# ds32djg.net
KiCad netlist of a schematic drawn in EAGLE
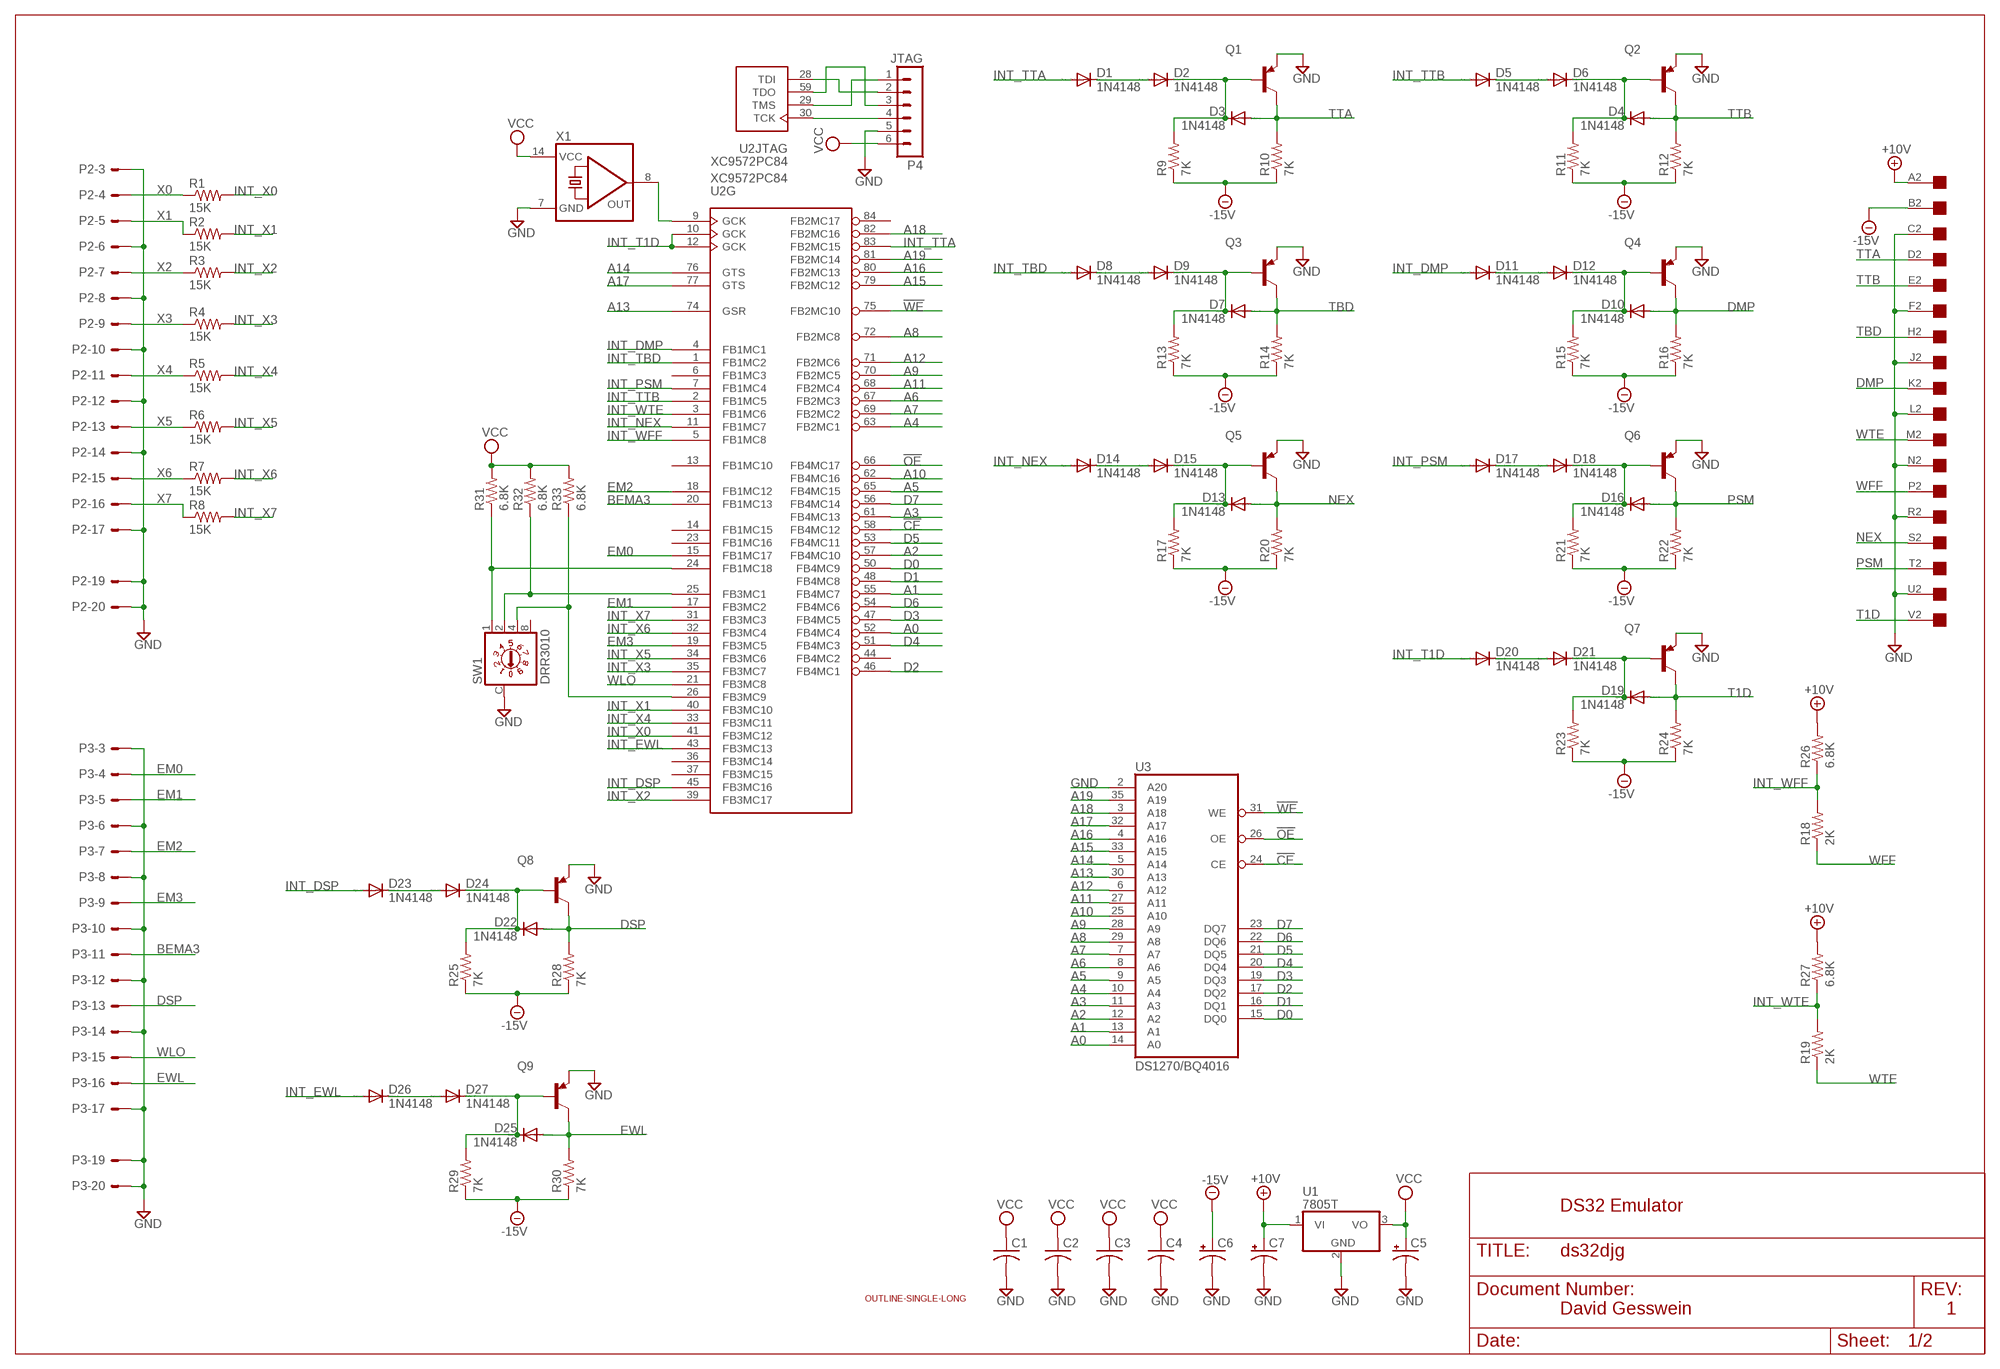
[diagram p0: schematic, sheet 1]
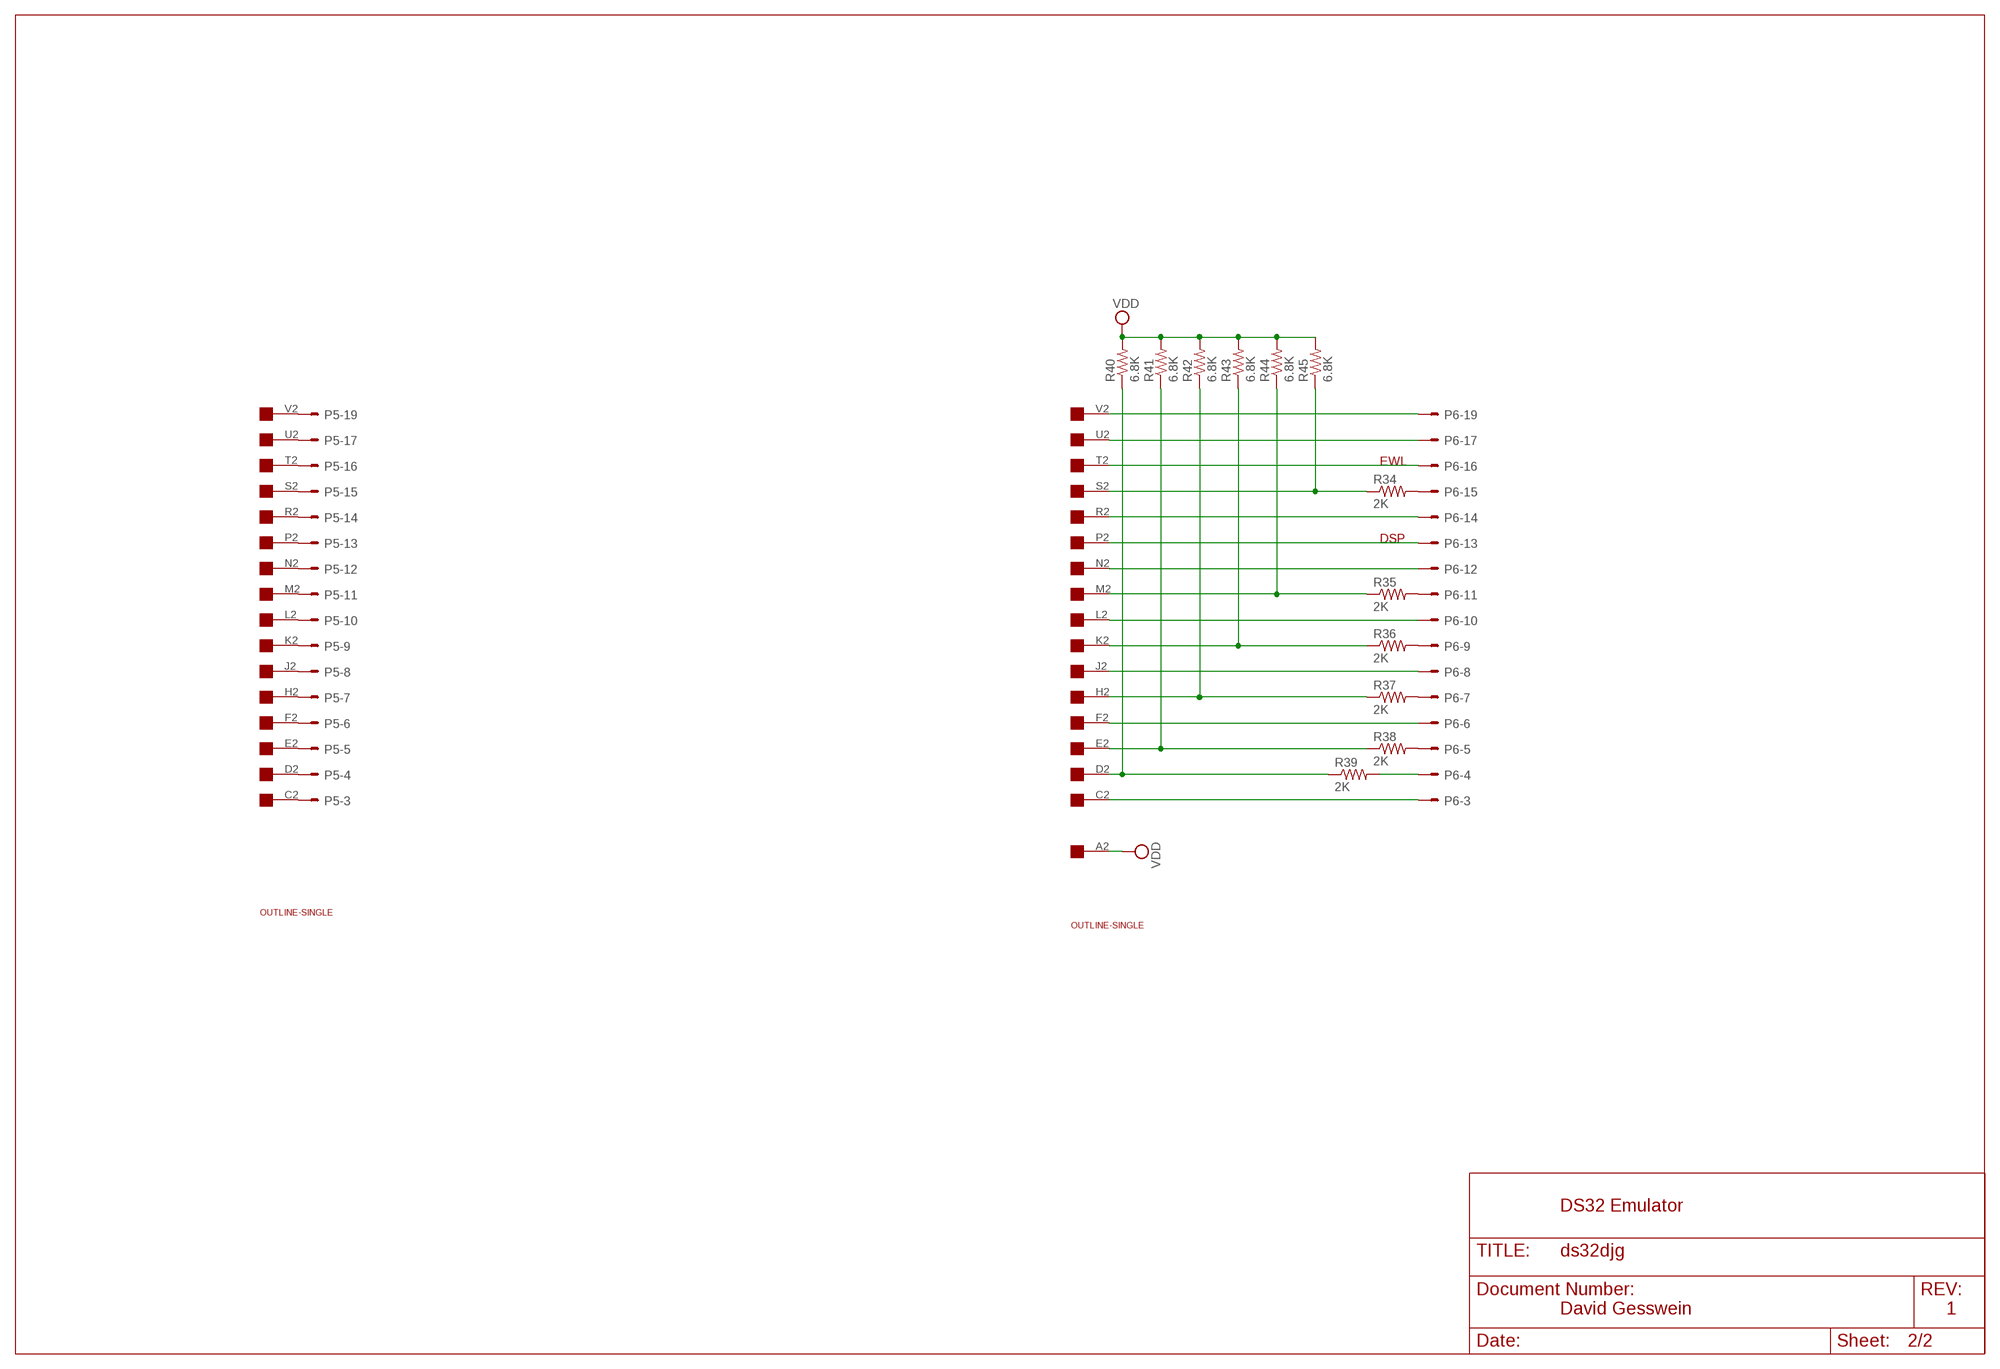
[diagram p1: schematic, sheet 2]

(export (version "E")
  (design (tool "Eeschema 10.0.6"))
  (components
    (comp (ref "P5")
      (value "ML20E")
      (footprint "eagle-import:ML20")
      (libsource (lib "eagle-import") (part "ML20?E"))
    )
    (comp (ref "P6")
      (value "ML20E")
      (footprint "eagle-import:ML20")
      (libsource (lib "eagle-import") (part "ML20?E"))
    )
    (comp (ref "R34")
      (value "2K")
      (footprint "eagle-import:0207_10")
      (libsource (lib "eagle-import") (part "R-US_0207/10"))
    )
    (comp (ref "R35")
      (value "2K")
      (footprint "eagle-import:0207_10")
      (libsource (lib "eagle-import") (part "R-US_0207/10"))
    )
    (comp (ref "R36")
      (value "2K")
      (footprint "eagle-import:0207_10")
      (libsource (lib "eagle-import") (part "R-US_0207/10"))
    )
    (comp (ref "R37")
      (value "2K")
      (footprint "eagle-import:0207_10")
      (libsource (lib "eagle-import") (part "R-US_0207/10"))
    )
    (comp (ref "R38")
      (value "2K")
      (footprint "eagle-import:0207_10")
      (libsource (lib "eagle-import") (part "R-US_0207/10"))
    )
    (comp (ref "R39")
      (value "2K")
      (footprint "eagle-import:0207_10")
      (libsource (lib "eagle-import") (part "R-US_0207/10"))
    )
    (comp (ref "R40")
      (value "6.8K")
      (footprint "eagle-import:0207_10")
      (libsource (lib "eagle-import") (part "R-US_0207/10"))
    )
    (comp (ref "R41")
      (value "6.8K")
      (footprint "eagle-import:0207_10")
      (libsource (lib "eagle-import") (part "R-US_0207/10"))
    )
    (comp (ref "R42")
      (value "6.8K")
      (footprint "eagle-import:0207_10")
      (libsource (lib "eagle-import") (part "R-US_0207/10"))
    )
    (comp (ref "R43")
      (value "6.8K")
      (footprint "eagle-import:0207_10")
      (libsource (lib "eagle-import") (part "R-US_0207/10"))
    )
    (comp (ref "R44")
      (value "6.8K")
      (footprint "eagle-import:0207_10")
      (libsource (lib "eagle-import") (part "R-US_0207/10"))
    )
    (comp (ref "R45")
      (value "6.8K")
      (footprint "eagle-import:0207_10")
      (libsource (lib "eagle-import") (part "R-US_0207/10"))
    )
    (comp (ref "U$1")
      (value "EDGE-1")
      (footprint "eagle-import:EDGE-CON1")
      (libsource (lib "eagle-import") (part "EDGE-1"))
    )
    (comp (ref "U$2")
      (value "EDGE-1")
      (footprint "eagle-import:EDGE-CON1")
      (libsource (lib "eagle-import") (part "EDGE-1"))
    )
    (comp (ref "U$4")
      (value "OUTLINE-SINGLE")
      (footprint "eagle-import:SINGLE")
      (libsource (lib "eagle-import") (part "OUTLINE-SINGLE"))
    )
    (comp (ref "U$5")
      (value "OUTLINE-SINGLE")
      (footprint "eagle-import:SINGLE")
      (libsource (lib "eagle-import") (part "OUTLINE-SINGLE"))
    )
    (comp (ref "C1")
      (value "C-US050-025X075")
      (footprint "eagle-import:C050-025X075")
      (libsource (lib "eagle-import") (part "C-US050-025X075"))
    )
    (comp (ref "C2")
      (value "C-US050-025X075")
      (footprint "eagle-import:C050-025X075")
      (libsource (lib "eagle-import") (part "C-US050-025X075"))
    )
    (comp (ref "C3")
      (value "C-US050-025X075")
      (footprint "eagle-import:C050-025X075")
      (libsource (lib "eagle-import") (part "C-US050-025X075"))
    )
    (comp (ref "C4")
      (value "C-US050-025X075")
      (footprint "eagle-import:C050-025X075")
      (libsource (lib "eagle-import") (part "C-US050-025X075"))
    )
    (comp (ref "C5")
      (value "CPOL-USE15-5AXIAL")
      (footprint "eagle-import:E15-5")
      (libsource (lib "eagle-import") (part "CPOL-USE15-5AXIAL"))
    )
    (comp (ref "C6")
      (value "CPOL-USE15-5AXIAL")
      (footprint "eagle-import:E15-5")
      (libsource (lib "eagle-import") (part "CPOL-USE15-5AXIAL"))
    )
    (comp (ref "C7")
      (value "CPOL-USE15-5AXIAL")
      (footprint "eagle-import:E15-5")
      (libsource (lib "eagle-import") (part "CPOL-USE15-5AXIAL"))
    )
    (comp (ref "D1")
      (value "1N4148")
      (footprint "eagle-import:DO35-10")
      (libsource (lib "eagle-import") (part "1N4148DO35-10"))
    )
    (comp (ref "D2")
      (value "1N4148")
      (footprint "eagle-import:DO35-10")
      (libsource (lib "eagle-import") (part "1N4148DO35-10"))
    )
    (comp (ref "D3")
      (value "1N4148")
      (footprint "eagle-import:DO35-10")
      (libsource (lib "eagle-import") (part "1N4148DO35-10"))
    )
    (comp (ref "D4")
      (value "1N4148")
      (footprint "eagle-import:DO35-10")
      (libsource (lib "eagle-import") (part "1N4148DO35-10"))
    )
    (comp (ref "D5")
      (value "1N4148")
      (footprint "eagle-import:DO35-10")
      (libsource (lib "eagle-import") (part "1N4148DO35-10"))
    )
    (comp (ref "D6")
      (value "1N4148")
      (footprint "eagle-import:DO35-10")
      (libsource (lib "eagle-import") (part "1N4148DO35-10"))
    )
    (comp (ref "D7")
      (value "1N4148")
      (footprint "eagle-import:DO35-10")
      (libsource (lib "eagle-import") (part "1N4148DO35-10"))
    )
    (comp (ref "D8")
      (value "1N4148")
      (footprint "eagle-import:DO35-10")
      (libsource (lib "eagle-import") (part "1N4148DO35-10"))
    )
    (comp (ref "D9")
      (value "1N4148")
      (footprint "eagle-import:DO35-10")
      (libsource (lib "eagle-import") (part "1N4148DO35-10"))
    )
    (comp (ref "D10")
      (value "1N4148")
      (footprint "eagle-import:DO35-10")
      (libsource (lib "eagle-import") (part "1N4148DO35-10"))
    )
    (comp (ref "D11")
      (value "1N4148")
      (footprint "eagle-import:DO35-10")
      (libsource (lib "eagle-import") (part "1N4148DO35-10"))
    )
    (comp (ref "D12")
      (value "1N4148")
      (footprint "eagle-import:DO35-10")
      (libsource (lib "eagle-import") (part "1N4148DO35-10"))
    )
    (comp (ref "D13")
      (value "1N4148")
      (footprint "eagle-import:DO35-10")
      (libsource (lib "eagle-import") (part "1N4148DO35-10"))
    )
    (comp (ref "D14")
      (value "1N4148")
      (footprint "eagle-import:DO35-10")
      (libsource (lib "eagle-import") (part "1N4148DO35-10"))
    )
    (comp (ref "D15")
      (value "1N4148")
      (footprint "eagle-import:DO35-10")
      (libsource (lib "eagle-import") (part "1N4148DO35-10"))
    )
    (comp (ref "D16")
      (value "1N4148")
      (footprint "eagle-import:DO35-10")
      (libsource (lib "eagle-import") (part "1N4148DO35-10"))
    )
    (comp (ref "D17")
      (value "1N4148")
      (footprint "eagle-import:DO35-10")
      (libsource (lib "eagle-import") (part "1N4148DO35-10"))
    )
    (comp (ref "D18")
      (value "1N4148")
      (footprint "eagle-import:DO35-10")
      (libsource (lib "eagle-import") (part "1N4148DO35-10"))
    )
    (comp (ref "D19")
      (value "1N4148")
      (footprint "eagle-import:DO35-10")
      (libsource (lib "eagle-import") (part "1N4148DO35-10"))
    )
    (comp (ref "D20")
      (value "1N4148")
      (footprint "eagle-import:DO35-10")
      (libsource (lib "eagle-import") (part "1N4148DO35-10"))
    )
    (comp (ref "D21")
      (value "1N4148")
      (footprint "eagle-import:DO35-10")
      (libsource (lib "eagle-import") (part "1N4148DO35-10"))
    )
    (comp (ref "D22")
      (value "1N4148")
      (footprint "eagle-import:DO35-10")
      (libsource (lib "eagle-import") (part "1N4148DO35-10"))
    )
    (comp (ref "D23")
      (value "1N4148")
      (footprint "eagle-import:DO35-10")
      (libsource (lib "eagle-import") (part "1N4148DO35-10"))
    )
    (comp (ref "D24")
      (value "1N4148")
      (footprint "eagle-import:DO35-10")
      (libsource (lib "eagle-import") (part "1N4148DO35-10"))
    )
    (comp (ref "D25")
      (value "1N4148")
      (footprint "eagle-import:DO35-10")
      (libsource (lib "eagle-import") (part "1N4148DO35-10"))
    )
    (comp (ref "D26")
      (value "1N4148")
      (footprint "eagle-import:DO35-10")
      (libsource (lib "eagle-import") (part "1N4148DO35-10"))
    )
    (comp (ref "D27")
      (value "1N4148")
      (footprint "eagle-import:DO35-10")
      (libsource (lib "eagle-import") (part "1N4148DO35-10"))
    )
    (comp (ref "P1")
      (value "EDGE-1")
      (footprint "eagle-import:EDGE-CON1")
      (libsource (lib "eagle-import") (part "EDGE-1"))
    )
    (comp (ref "P2")
      (value "ML20E")
      (footprint "eagle-import:ML20")
      (libsource (lib "eagle-import") (part "ML20?E"))
    )
    (comp (ref "P3")
      (value "ML20E")
      (footprint "eagle-import:ML20")
      (libsource (lib "eagle-import") (part "ML20?E"))
    )
    (comp (ref "P4")
      (value "JTAG")
      (footprint "eagle-import:MA06-1")
      (libsource (lib "eagle-import") (part "MA06-1"))
    )
    (comp (ref "Q1")
      (value "-PNP-TO92/")
      (footprint "eagle-import:TO92_")
      (libsource (lib "eagle-import") (part "-PNP-TO92/"))
    )
    (comp (ref "Q2")
      (value "-PNP-TO92/")
      (footprint "eagle-import:TO92_")
      (libsource (lib "eagle-import") (part "-PNP-TO92/"))
    )
    (comp (ref "Q3")
      (value "-PNP-TO92/")
      (footprint "eagle-import:TO92_")
      (libsource (lib "eagle-import") (part "-PNP-TO92/"))
    )
    (comp (ref "Q4")
      (value "-PNP-TO92/")
      (footprint "eagle-import:TO92_")
      (libsource (lib "eagle-import") (part "-PNP-TO92/"))
    )
    (comp (ref "Q5")
      (value "-PNP-TO92/")
      (footprint "eagle-import:TO92_")
      (libsource (lib "eagle-import") (part "-PNP-TO92/"))
    )
    (comp (ref "Q6")
      (value "-PNP-TO92/")
      (footprint "eagle-import:TO92_")
      (libsource (lib "eagle-import") (part "-PNP-TO92/"))
    )
    (comp (ref "Q7")
      (value "-PNP-TO92/")
      (footprint "eagle-import:TO92_")
      (libsource (lib "eagle-import") (part "-PNP-TO92/"))
    )
    (comp (ref "Q8")
      (value "-PNP-TO92/")
      (footprint "eagle-import:TO92_")
      (libsource (lib "eagle-import") (part "-PNP-TO92/"))
    )
    (comp (ref "Q9")
      (value "-PNP-TO92/")
      (footprint "eagle-import:TO92_")
      (libsource (lib "eagle-import") (part "-PNP-TO92/"))
    )
    (comp (ref "R1")
      (value "15K")
      (footprint "eagle-import:0207_10")
      (libsource (lib "eagle-import") (part "R-US_0207/10"))
    )
    (comp (ref "R2")
      (value "15K")
      (footprint "eagle-import:0207_10")
      (libsource (lib "eagle-import") (part "R-US_0207/10"))
    )
    (comp (ref "R3")
      (value "15K")
      (footprint "eagle-import:0207_10")
      (libsource (lib "eagle-import") (part "R-US_0207/10"))
    )
    (comp (ref "R4")
      (value "15K")
      (footprint "eagle-import:0207_10")
      (libsource (lib "eagle-import") (part "R-US_0207/10"))
    )
    (comp (ref "R5")
      (value "15K")
      (footprint "eagle-import:0207_10")
      (libsource (lib "eagle-import") (part "R-US_0207/10"))
    )
    (comp (ref "R6")
      (value "15K")
      (footprint "eagle-import:0207_10")
      (libsource (lib "eagle-import") (part "R-US_0207/10"))
    )
    (comp (ref "R7")
      (value "15K")
      (footprint "eagle-import:0207_10")
      (libsource (lib "eagle-import") (part "R-US_0207/10"))
    )
    (comp (ref "R8")
      (value "15K")
      (footprint "eagle-import:0207_10")
      (libsource (lib "eagle-import") (part "R-US_0207/10"))
    )
    (comp (ref "R9")
      (value "7K")
      (footprint "eagle-import:0207_10")
      (libsource (lib "eagle-import") (part "R-US_0207/10"))
    )
    (comp (ref "R10")
      (value "7K")
      (footprint "eagle-import:0207_10")
      (libsource (lib "eagle-import") (part "R-US_0207/10"))
    )
    (comp (ref "R11")
      (value "7K")
      (footprint "eagle-import:0207_10")
      (libsource (lib "eagle-import") (part "R-US_0207/10"))
    )
    (comp (ref "R12")
      (value "7K")
      (footprint "eagle-import:0207_10")
      (libsource (lib "eagle-import") (part "R-US_0207/10"))
    )
    (comp (ref "R13")
      (value "7K")
      (footprint "eagle-import:0207_10")
      (libsource (lib "eagle-import") (part "R-US_0207/10"))
    )
    (comp (ref "R14")
      (value "7K")
      (footprint "eagle-import:0207_10")
      (libsource (lib "eagle-import") (part "R-US_0207/10"))
    )
    (comp (ref "R15")
      (value "7K")
      (footprint "eagle-import:0207_10")
      (libsource (lib "eagle-import") (part "R-US_0207/10"))
    )
    (comp (ref "R16")
      (value "7K")
      (footprint "eagle-import:0207_10")
      (libsource (lib "eagle-import") (part "R-US_0207/10"))
    )
    (comp (ref "R17")
      (value "7K")
      (footprint "eagle-import:0207_10")
      (libsource (lib "eagle-import") (part "R-US_0207/10"))
    )
    (comp (ref "R18")
      (value "2K")
      (footprint "eagle-import:0207_10")
      (libsource (lib "eagle-import") (part "R-US_0207/10"))
    )
    (comp (ref "R19")
      (value "2K")
      (footprint "eagle-import:0207_10")
      (libsource (lib "eagle-import") (part "R-US_0207/10"))
    )
    (comp (ref "R20")
      (value "7K")
      (footprint "eagle-import:0207_10")
      (libsource (lib "eagle-import") (part "R-US_0207/10"))
    )
    (comp (ref "R21")
      (value "7K")
      (footprint "eagle-import:0207_10")
      (libsource (lib "eagle-import") (part "R-US_0207/10"))
    )
    (comp (ref "R22")
      (value "7K")
      (footprint "eagle-import:0207_10")
      (libsource (lib "eagle-import") (part "R-US_0207/10"))
    )
    (comp (ref "R23")
      (value "7K")
      (footprint "eagle-import:0207_10")
      (libsource (lib "eagle-import") (part "R-US_0207/10"))
    )
    (comp (ref "R24")
      (value "7K")
      (footprint "eagle-import:0207_10")
      (libsource (lib "eagle-import") (part "R-US_0207/10"))
    )
    (comp (ref "R25")
      (value "7K")
      (footprint "eagle-import:0207_10")
      (libsource (lib "eagle-import") (part "R-US_0207/10"))
    )
    (comp (ref "R26")
      (value "6.8K")
      (footprint "eagle-import:0207_10")
      (libsource (lib "eagle-import") (part "R-US_0207/10"))
    )
    (comp (ref "R27")
      (value "6.8K")
      (footprint "eagle-import:0207_10")
      (libsource (lib "eagle-import") (part "R-US_0207/10"))
    )
    (comp (ref "R28")
      (value "7K")
      (footprint "eagle-import:0207_10")
      (libsource (lib "eagle-import") (part "R-US_0207/10"))
    )
    (comp (ref "R29")
      (value "7K")
      (footprint "eagle-import:0207_10")
      (libsource (lib "eagle-import") (part "R-US_0207/10"))
    )
    (comp (ref "R30")
      (value "7K")
      (footprint "eagle-import:0207_10")
      (libsource (lib "eagle-import") (part "R-US_0207/10"))
    )
    (comp (ref "R31")
      (value "6.8K")
      (footprint "eagle-import:0207_10")
      (libsource (lib "eagle-import") (part "R-US_0207/10"))
    )
    (comp (ref "R32")
      (value "6.8K")
      (footprint "eagle-import:0207_10")
      (libsource (lib "eagle-import") (part "R-US_0207/10"))
    )
    (comp (ref "R33")
      (value "6.8K")
      (footprint "eagle-import:0207_10")
      (libsource (lib "eagle-import") (part "R-US_0207/10"))
    )
    (comp (ref "SW1")
      (value "DRR3010")
      (footprint "eagle-import:DRR3010")
      (libsource (lib "eagle-import") (part "DRR3010"))
    )
    (comp (ref "U$3")
      (value "OUTLINE-SINGLE-LONG")
      (footprint "eagle-import:SINGLE-LONG")
      (libsource (lib "eagle-import") (part "OUTLINE-SINGLE-LONG"))
    )
    (comp (ref "U1")
      (value "7805T")
      (footprint "eagle-import:TO220H")
      (libsource (lib "eagle-import") (part "78T05"))
    )
    (comp (ref "U2")
      (value "XC9572PC84")
      (footprint "eagle-import:PLCC-S84")
      (libsource (lib "eagle-import") (part "XC9572PC84"))
    )
    (comp (ref "U3")
      (value "DS1270/BQ4016")
      (footprint "eagle-import:MIL740EXT36")
      (libsource (lib "eagle-import") (part "DS1270"))
    )
    (comp (ref "X1")
      (value "QG5860")
      (footprint "eagle-import:DIL14S")
      (libsource (lib "eagle-import") (part "QG5860"))
    )
  )
  (nets
    (net (code "1") (name "+10V") (class "Default")
      (node (ref "C7") (pin "+") (pinfunction "+_+") (pintype "passive"))
      (node (ref "P1") (pin "A2") (pinfunction "1_A2") (pintype "bidirectional"))
      (node (ref "R26") (pin "2") (pinfunction "2_2") (pintype "passive"))
      (node (ref "R27") (pin "2") (pinfunction "2_2") (pintype "passive"))
      (node (ref "U1") (pin "1") (pinfunction "VI_1") (pintype "input"))
    )
    (net (code "2") (name "-15V") (class "Default")
      (node (ref "C6") (pin "+") (pinfunction "+_+") (pintype "passive"))
      (node (ref "P1") (pin "B2") (pinfunction "1_B2") (pintype "bidirectional"))
      (node (ref "R10") (pin "1") (pinfunction "1_1") (pintype "passive"))
      (node (ref "R11") (pin "1") (pinfunction "1_1") (pintype "passive"))
      (node (ref "R12") (pin "1") (pinfunction "1_1") (pintype "passive"))
      (node (ref "R13") (pin "1") (pinfunction "1_1") (pintype "passive"))
      (node (ref "R14") (pin "1") (pinfunction "1_1") (pintype "passive"))
      (node (ref "R15") (pin "1") (pinfunction "1_1") (pintype "passive"))
      (node (ref "R16") (pin "1") (pinfunction "1_1") (pintype "passive"))
      (node (ref "R17") (pin "1") (pinfunction "1_1") (pintype "passive"))
      (node (ref "R20") (pin "1") (pinfunction "1_1") (pintype "passive"))
      (node (ref "R21") (pin "1") (pinfunction "1_1") (pintype "passive"))
      (node (ref "R22") (pin "1") (pinfunction "1_1") (pintype "passive"))
      (node (ref "R23") (pin "1") (pinfunction "1_1") (pintype "passive"))
      (node (ref "R24") (pin "1") (pinfunction "1_1") (pintype "passive"))
      (node (ref "R25") (pin "1") (pinfunction "1_1") (pintype "passive"))
      (node (ref "R28") (pin "1") (pinfunction "1_1") (pintype "passive"))
      (node (ref "R29") (pin "1") (pinfunction "1_1") (pintype "passive"))
      (node (ref "R30") (pin "1") (pinfunction "1_1") (pintype "passive"))
      (node (ref "R9") (pin "1") (pinfunction "1_1") (pintype "passive"))
    )
    (net (code "3") (name "A0") (class "Default")
      (node (ref "U2") (pin "52") (pinfunction "FB4MC4_52") (pintype "bidirectional"))
      (node (ref "U3") (pin "14") (pinfunction "A0_14") (pintype "input"))
    )
    (net (code "4") (name "A1") (class "Default")
      (node (ref "U2") (pin "55") (pinfunction "FB4MC7_55") (pintype "bidirectional"))
      (node (ref "U3") (pin "13") (pinfunction "A1_13") (pintype "input"))
    )
    (net (code "5") (name "A2") (class "Default")
      (node (ref "U2") (pin "57") (pinfunction "FB4MC10_57") (pintype "bidirectional"))
      (node (ref "U3") (pin "12") (pinfunction "A2_12") (pintype "input"))
    )
    (net (code "6") (name "A3") (class "Default")
      (node (ref "U2") (pin "61") (pinfunction "FB4MC13_61") (pintype "bidirectional"))
      (node (ref "U3") (pin "11") (pinfunction "A3_11") (pintype "input"))
    )
    (net (code "7") (name "A4") (class "Default")
      (node (ref "U2") (pin "63") (pinfunction "FB2MC1_63") (pintype "bidirectional"))
      (node (ref "U3") (pin "10") (pinfunction "A4_10") (pintype "input"))
    )
    (net (code "8") (name "A5") (class "Default")
      (node (ref "U2") (pin "65") (pinfunction "FB4MC15_65") (pintype "bidirectional"))
      (node (ref "U3") (pin "9") (pinfunction "A5_9") (pintype "input"))
    )
    (net (code "9") (name "A6") (class "Default")
      (node (ref "U2") (pin "67") (pinfunction "FB2MC3_67") (pintype "bidirectional"))
      (node (ref "U3") (pin "8") (pinfunction "A6_8") (pintype "input"))
    )
    (net (code "10") (name "A7") (class "Default")
      (node (ref "U2") (pin "69") (pinfunction "FB2MC2_69") (pintype "bidirectional"))
      (node (ref "U3") (pin "7") (pinfunction "A7_7") (pintype "input"))
    )
    (net (code "11") (name "A8") (class "Default")
      (node (ref "U2") (pin "72") (pinfunction "FB2MC8_72") (pintype "bidirectional"))
      (node (ref "U3") (pin "29") (pinfunction "A8_29") (pintype "input"))
    )
    (net (code "12") (name "A9") (class "Default")
      (node (ref "U2") (pin "70") (pinfunction "FB2MC5_70") (pintype "bidirectional"))
      (node (ref "U3") (pin "28") (pinfunction "A9_28") (pintype "input"))
    )
    (net (code "13") (name "A10") (class "Default")
      (node (ref "U2") (pin "62") (pinfunction "FB4MC16_62") (pintype "bidirectional"))
      (node (ref "U3") (pin "25") (pinfunction "A10_25") (pintype "input"))
    )
    (net (code "14") (name "A11") (class "Default")
      (node (ref "U2") (pin "68") (pinfunction "FB2MC4_68") (pintype "bidirectional"))
      (node (ref "U3") (pin "27") (pinfunction "A11_27") (pintype "input"))
    )
    (net (code "15") (name "A12") (class "Default")
      (node (ref "U2") (pin "71") (pinfunction "FB2MC6_71") (pintype "bidirectional"))
      (node (ref "U3") (pin "6") (pinfunction "A12_6") (pintype "input"))
    )
    (net (code "16") (name "A13") (class "Default")
      (node (ref "U2") (pin "74") (pinfunction "GSR_74") (pintype "input"))
      (node (ref "U3") (pin "30") (pinfunction "A13_30") (pintype "input"))
    )
    (net (code "17") (name "A14") (class "Default")
      (node (ref "U2") (pin "76") (pinfunction "GTS_76") (pintype "input"))
      (node (ref "U3") (pin "5") (pinfunction "A14_5") (pintype "input"))
    )
    (net (code "18") (name "A15") (class "Default")
      (node (ref "U2") (pin "79") (pinfunction "FB2MC12_79") (pintype "bidirectional"))
      (node (ref "U3") (pin "33") (pinfunction "A15_33") (pintype "input"))
    )
    (net (code "19") (name "A16") (class "Default")
      (node (ref "U2") (pin "80") (pinfunction "FB2MC13_80") (pintype "bidirectional"))
      (node (ref "U3") (pin "4") (pinfunction "A16_4") (pintype "input"))
    )
    (net (code "20") (name "A17") (class "Default")
      (node (ref "U2") (pin "77") (pinfunction "GTS_77") (pintype "input"))
      (node (ref "U3") (pin "32") (pinfunction "A17_32") (pintype "input"))
    )
    (net (code "21") (name "A18") (class "Default")
      (node (ref "U2") (pin "82") (pinfunction "FB2MC16_82") (pintype "bidirectional"))
      (node (ref "U3") (pin "3") (pinfunction "A18_3") (pintype "input"))
    )
    (net (code "22") (name "A19") (class "Default")
      (node (ref "U2") (pin "81") (pinfunction "FB2MC14_81") (pintype "bidirectional"))
      (node (ref "U3") (pin "35") (pinfunction "A19_35") (pintype "input"))
    )
    (net (code "23") (name "BEMA3") (class "Default")
      (node (ref "P3") (pin "11") (pinfunction "S_11") (pintype "passive"))
      (node (ref "U2") (pin "20") (pinfunction "FB1MC13_20") (pintype "bidirectional"))
    )
    (net (code "24") (name "D0") (class "Default")
      (node (ref "U2") (pin "50") (pinfunction "FB4MC9_50") (pintype "bidirectional"))
      (node (ref "U3") (pin "15") (pinfunction "DQ0_15") (pintype "bidirectional"))
    )
    (net (code "25") (name "D1") (class "Default")
      (node (ref "U2") (pin "48") (pinfunction "FB4MC8_48") (pintype "bidirectional"))
      (node (ref "U3") (pin "16") (pinfunction "DQ1_16") (pintype "bidirectional"))
    )
    (net (code "26") (name "D2") (class "Default")
      (node (ref "U2") (pin "46") (pinfunction "FB4MC1_46") (pintype "bidirectional"))
      (node (ref "U3") (pin "17") (pinfunction "DQ2_17") (pintype "bidirectional"))
    )
    (net (code "27") (name "D3") (class "Default")
      (node (ref "U2") (pin "47") (pinfunction "FB4MC5_47") (pintype "bidirectional"))
      (node (ref "U3") (pin "19") (pinfunction "DQ3_19") (pintype "bidirectional"))
    )
    (net (code "28") (name "D4") (class "Default")
      (node (ref "U2") (pin "51") (pinfunction "FB4MC3_51") (pintype "bidirectional"))
      (node (ref "U3") (pin "20") (pinfunction "DQ4_20") (pintype "bidirectional"))
    )
    (net (code "29") (name "D5") (class "Default")
      (node (ref "U2") (pin "53") (pinfunction "FB4MC11_53") (pintype "bidirectional"))
      (node (ref "U3") (pin "21") (pinfunction "DQ5_21") (pintype "bidirectional"))
    )
    (net (code "30") (name "D6") (class "Default")
      (node (ref "U2") (pin "54") (pinfunction "FB4MC6_54") (pintype "bidirectional"))
      (node (ref "U3") (pin "22") (pinfunction "DQ6_22") (pintype "bidirectional"))
    )
    (net (code "31") (name "D7") (class "Default")
      (node (ref "U2") (pin "56") (pinfunction "FB4MC14_56") (pintype "bidirectional"))
      (node (ref "U3") (pin "23") (pinfunction "DQ7_23") (pintype "bidirectional"))
    )
    (net (code "32") (name "DMP") (class "Default")
      (node (ref "D10") (pin "A") (pinfunction "A_A") (pintype "passive"))
      (node (ref "P1") (pin "K2") (pinfunction "1_K2") (pintype "bidirectional"))
      (node (ref "Q4") (pin "3") (pinfunction "C_3") (pintype "passive"))
      (node (ref "R16") (pin "2") (pinfunction "2_2") (pintype "passive"))
    )
    (net (code "33") (name "DSP") (class "Default")
      (node (ref "D22") (pin "A") (pinfunction "A_A") (pintype "passive"))
      (node (ref "P3") (pin "13") (pinfunction "S_13") (pintype "passive"))
      (node (ref "Q8") (pin "3") (pinfunction "C_3") (pintype "passive"))
      (node (ref "R28") (pin "2") (pinfunction "2_2") (pintype "passive"))
    )
    (net (code "34") (name "EM0") (class "Default")
      (node (ref "P3") (pin "4") (pinfunction "S_4") (pintype "passive"))
      (node (ref "U2") (pin "15") (pinfunction "FB1MC17_15") (pintype "bidirectional"))
    )
    (net (code "35") (name "EM1") (class "Default")
      (node (ref "P3") (pin "5") (pinfunction "S_5") (pintype "passive"))
      (node (ref "U2") (pin "17") (pinfunction "FB3MC2_17") (pintype "bidirectional"))
    )
    (net (code "36") (name "EM2") (class "Default")
      (node (ref "P3") (pin "7") (pinfunction "S_7") (pintype "passive"))
      (node (ref "U2") (pin "18") (pinfunction "FB1MC12_18") (pintype "bidirectional"))
    )
    (net (code "37") (name "EM3") (class "Default")
      (node (ref "P3") (pin "9") (pinfunction "S_9") (pintype "passive"))
      (node (ref "U2") (pin "19") (pinfunction "FB3MC5_19") (pintype "bidirectional"))
    )
    (net (code "38") (name "EWL") (class "Default")
      (node (ref "D25") (pin "A") (pinfunction "A_A") (pintype "passive"))
      (node (ref "P3") (pin "16") (pinfunction "S_16") (pintype "passive"))
      (node (ref "Q9") (pin "3") (pinfunction "C_3") (pintype "passive"))
      (node (ref "R30") (pin "2") (pinfunction "2_2") (pintype "passive"))
    )
    (net (code "39") (name "GND") (class "Default")
      (node (ref "C1") (pin "2") (pinfunction "2_2") (pintype "passive"))
      (node (ref "C2") (pin "2") (pinfunction "2_2") (pintype "passive"))
      (node (ref "C3") (pin "2") (pinfunction "2_2") (pintype "passive"))
      (node (ref "C4") (pin "2") (pinfunction "2_2") (pintype "passive"))
      (node (ref "C5") (pin "-") (pinfunction "-_-") (pintype "passive"))
      (node (ref "C6") (pin "-") (pinfunction "-_-") (pintype "passive"))
      (node (ref "C7") (pin "-") (pinfunction "-_-") (pintype "passive"))
      (node (ref "P1") (pin "C2") (pinfunction "1_C2") (pintype "bidirectional"))
      (node (ref "P1") (pin "F2") (pinfunction "1_F2") (pintype "bidirectional"))
      (node (ref "P1") (pin "J2") (pinfunction "1_J2") (pintype "bidirectional"))
      (node (ref "P1") (pin "L2") (pinfunction "1_L2") (pintype "bidirectional"))
      (node (ref "P1") (pin "N2") (pinfunction "1_N2") (pintype "bidirectional"))
      (node (ref "P1") (pin "R2") (pinfunction "1_R2") (pintype "bidirectional"))
      (node (ref "P1") (pin "U2") (pinfunction "1_U2") (pintype "bidirectional"))
      (node (ref "P2") (pin "10") (pinfunction "S_10") (pintype "passive"))
      (node (ref "P2") (pin "12") (pinfunction "S_12") (pintype "passive"))
      (node (ref "P2") (pin "14") (pinfunction "S_14") (pintype "passive"))
      (node (ref "P2") (pin "17") (pinfunction "S_17") (pintype "passive"))
      (node (ref "P2") (pin "19") (pinfunction "S_19") (pintype "passive"))
      (node (ref "P2") (pin "20") (pinfunction "S_20") (pintype "passive"))
      (node (ref "P2") (pin "3") (pinfunction "S_3") (pintype "passive"))
      (node (ref "P2") (pin "6") (pinfunction "S_6") (pintype "passive"))
      (node (ref "P2") (pin "8") (pinfunction "S_8") (pintype "passive"))
      (node (ref "P3") (pin "10") (pinfunction "S_10") (pintype "passive"))
      (node (ref "P3") (pin "12") (pinfunction "S_12") (pintype "passive"))
      (node (ref "P3") (pin "14") (pinfunction "S_14") (pintype "passive"))
      (node (ref "P3") (pin "17") (pinfunction "S_17") (pintype "passive"))
      (node (ref "P3") (pin "19") (pinfunction "S_19") (pintype "passive"))
      (node (ref "P3") (pin "20") (pinfunction "S_20") (pintype "passive"))
      (node (ref "P3") (pin "3") (pinfunction "S_3") (pintype "passive"))
      (node (ref "P3") (pin "6") (pinfunction "S_6") (pintype "passive"))
      (node (ref "P3") (pin "8") (pinfunction "S_8") (pintype "passive"))
      (node (ref "P4") (pin "5") (pinfunction "5_5") (pintype "passive"))
      (node (ref "Q1") (pin "1") (pinfunction "E_1") (pintype "passive"))
      (node (ref "Q2") (pin "1") (pinfunction "E_1") (pintype "passive"))
      (node (ref "Q3") (pin "1") (pinfunction "E_1") (pintype "passive"))
      (node (ref "Q4") (pin "1") (pinfunction "E_1") (pintype "passive"))
      (node (ref "Q5") (pin "1") (pinfunction "E_1") (pintype "passive"))
      (node (ref "Q6") (pin "1") (pinfunction "E_1") (pintype "passive"))
      (node (ref "Q7") (pin "1") (pinfunction "E_1") (pintype "passive"))
      (node (ref "Q8") (pin "1") (pinfunction "E_1") (pintype "passive"))
      (node (ref "Q9") (pin "1") (pinfunction "E_1") (pintype "passive"))
      (node (ref "SW1") (pin "C") (pinfunction "C_C") (pintype "passive"))
      (node (ref "U1") (pin "2") (pinfunction "GND_2") (pintype "passive"))
      (node (ref "U3") (pin "2") (pinfunction "A20_2") (pintype "input"))
      (node (ref "X1") (pin "7") (pinfunction "GND_7") (pintype "power_in"))
    )
    (net (code "40") (name "INT_DMP") (class "Default")
      (node (ref "D11") (pin "A") (pinfunction "A_A") (pintype "passive"))
      (node (ref "U2") (pin "4") (pinfunction "FB1MC1_4") (pintype "bidirectional"))
    )
    (net (code "41") (name "INT_DSP") (class "Default")
      (node (ref "D23") (pin "A") (pinfunction "A_A") (pintype "passive"))
      (node (ref "U2") (pin "45") (pinfunction "FB3MC16_45") (pintype "bidirectional"))
    )
    (net (code "42") (name "INT_EWL") (class "Default")
      (node (ref "D26") (pin "A") (pinfunction "A_A") (pintype "passive"))
      (node (ref "U2") (pin "43") (pinfunction "FB3MC13_43") (pintype "bidirectional"))
    )
    (net (code "43") (name "INT_NEX") (class "Default")
      (node (ref "D14") (pin "A") (pinfunction "A_A") (pintype "passive"))
      (node (ref "U2") (pin "11") (pinfunction "FB1MC7_11") (pintype "bidirectional"))
    )
    (net (code "44") (name "INT_PSM") (class "Default")
      (node (ref "D17") (pin "A") (pinfunction "A_A") (pintype "passive"))
      (node (ref "U2") (pin "7") (pinfunction "FB1MC4_7") (pintype "bidirectional"))
    )
    (net (code "45") (name "INT_T1D") (class "Default")
      (node (ref "D20") (pin "A") (pinfunction "A_A") (pintype "passive"))
      (node (ref "U2") (pin "10") (pinfunction "GCK_10") (pintype "input"))
      (node (ref "U2") (pin "12") (pinfunction "GCK_12") (pintype "input"))
    )
    (net (code "46") (name "INT_TBD") (class "Default")
      (node (ref "D8") (pin "A") (pinfunction "A_A") (pintype "passive"))
      (node (ref "U2") (pin "1") (pinfunction "FB1MC2_1") (pintype "bidirectional"))
    )
    (net (code "47") (name "INT_TTA") (class "Default")
      (node (ref "D1") (pin "A") (pinfunction "A_A") (pintype "passive"))
      (node (ref "U2") (pin "83") (pinfunction "FB2MC15_83") (pintype "bidirectional"))
    )
    (net (code "48") (name "INT_TTB") (class "Default")
      (node (ref "D5") (pin "A") (pinfunction "A_A") (pintype "passive"))
      (node (ref "U2") (pin "2") (pinfunction "FB1MC5_2") (pintype "bidirectional"))
    )
    (net (code "49") (name "INT_WFF") (class "Default")
      (node (ref "R18") (pin "2") (pinfunction "2_2") (pintype "passive"))
      (node (ref "R26") (pin "1") (pinfunction "1_1") (pintype "passive"))
      (node (ref "U2") (pin "5") (pinfunction "FB1MC8_5") (pintype "bidirectional"))
    )
    (net (code "50") (name "INT_WTE") (class "Default")
      (node (ref "R19") (pin "2") (pinfunction "2_2") (pintype "passive"))
      (node (ref "R27") (pin "1") (pinfunction "1_1") (pintype "passive"))
      (node (ref "U2") (pin "3") (pinfunction "FB1MC6_3") (pintype "bidirectional"))
    )
    (net (code "51") (name "INT_X0") (class "Default")
      (node (ref "R1") (pin "2") (pinfunction "2_2") (pintype "passive"))
      (node (ref "U2") (pin "41") (pinfunction "FB3MC12_41") (pintype "bidirectional"))
    )
    (net (code "52") (name "INT_X1") (class "Default")
      (node (ref "R2") (pin "2") (pinfunction "2_2") (pintype "passive"))
      (node (ref "U2") (pin "40") (pinfunction "FB3MC10_40") (pintype "bidirectional"))
    )
    (net (code "53") (name "INT_X2") (class "Default")
      (node (ref "R3") (pin "2") (pinfunction "2_2") (pintype "passive"))
      (node (ref "U2") (pin "39") (pinfunction "FB3MC17_39") (pintype "bidirectional"))
    )
    (net (code "54") (name "INT_X3") (class "Default")
      (node (ref "R4") (pin "2") (pinfunction "2_2") (pintype "passive"))
      (node (ref "U2") (pin "35") (pinfunction "FB3MC7_35") (pintype "bidirectional"))
    )
    (net (code "55") (name "INT_X4") (class "Default")
      (node (ref "R5") (pin "2") (pinfunction "2_2") (pintype "passive"))
      (node (ref "U2") (pin "33") (pinfunction "FB3MC11_33") (pintype "bidirectional"))
    )
    (net (code "56") (name "INT_X5") (class "Default")
      (node (ref "R6") (pin "2") (pinfunction "2_2") (pintype "passive"))
      (node (ref "U2") (pin "34") (pinfunction "FB3MC6_34") (pintype "bidirectional"))
    )
    (net (code "57") (name "INT_X6") (class "Default")
      (node (ref "R7") (pin "2") (pinfunction "2_2") (pintype "passive"))
      (node (ref "U2") (pin "32") (pinfunction "FB3MC4_32") (pintype "bidirectional"))
    )
    (net (code "58") (name "INT_X7") (class "Default")
      (node (ref "R8") (pin "2") (pinfunction "2_2") (pintype "passive"))
      (node (ref "U2") (pin "31") (pinfunction "FB3MC3_31") (pintype "bidirectional"))
    )
    (net (code "59") (name "NEX") (class "Default")
      (node (ref "D13") (pin "A") (pinfunction "A_A") (pintype "passive"))
      (node (ref "P1") (pin "S2") (pinfunction "1_S2") (pintype "bidirectional"))
      (node (ref "Q5") (pin "3") (pinfunction "C_3") (pintype "passive"))
      (node (ref "R20") (pin "2") (pinfunction "2_2") (pintype "passive"))
    )
    (net (code "60") (name "Net-(D1-PadC)") (class "Default")
      (node (ref "D1") (pin "C") (pinfunction "C_C") (pintype "passive"))
      (node (ref "D2") (pin "A") (pinfunction "A_A") (pintype "passive"))
    )
    (net (code "61") (name "Net-(D5-PadC)") (class "Default")
      (node (ref "D5") (pin "C") (pinfunction "C_C") (pintype "passive"))
      (node (ref "D6") (pin "A") (pinfunction "A_A") (pintype "passive"))
    )
    (net (code "62") (name "Net-(D8-PadC)") (class "Default")
      (node (ref "D8") (pin "C") (pinfunction "C_C") (pintype "passive"))
      (node (ref "D9") (pin "A") (pinfunction "A_A") (pintype "passive"))
    )
    (net (code "63") (name "Net-(D11-PadC)") (class "Default")
      (node (ref "D11") (pin "C") (pinfunction "C_C") (pintype "passive"))
      (node (ref "D12") (pin "A") (pinfunction "A_A") (pintype "passive"))
    )
    (net (code "64") (name "Net-(D14-PadC)") (class "Default")
      (node (ref "D14") (pin "C") (pinfunction "C_C") (pintype "passive"))
      (node (ref "D15") (pin "A") (pinfunction "A_A") (pintype "passive"))
    )
    (net (code "65") (name "Net-(D17-PadC)") (class "Default")
      (node (ref "D17") (pin "C") (pinfunction "C_C") (pintype "passive"))
      (node (ref "D18") (pin "A") (pinfunction "A_A") (pintype "passive"))
    )
    (net (code "66") (name "Net-(D20-PadC)") (class "Default")
      (node (ref "D20") (pin "C") (pinfunction "C_C") (pintype "passive"))
      (node (ref "D21") (pin "A") (pinfunction "A_A") (pintype "passive"))
    )
    (net (code "67") (name "Net-(D23-PadC)") (class "Default")
      (node (ref "D23") (pin "C") (pinfunction "C_C") (pintype "passive"))
      (node (ref "D24") (pin "A") (pinfunction "A_A") (pintype "passive"))
    )
    (net (code "68") (name "Net-(D26-PadC)") (class "Default")
      (node (ref "D26") (pin "C") (pinfunction "C_C") (pintype "passive"))
      (node (ref "D27") (pin "A") (pinfunction "A_A") (pintype "passive"))
    )
    (net (code "69") (name "Net-(P5B-S)") (class "Default")
      (node (ref "P5") (pin "10") (pinfunction "S_10") (pintype "passive"))
      (node (ref "U$1") (pin "L2") (pinfunction "1_L2") (pintype "bidirectional"))
    )
    (net (code "70") (name "Net-(P5C-S)") (class "Default")
      (node (ref "P5") (pin "11") (pinfunction "S_11") (pintype "passive"))
      (node (ref "U$1") (pin "M2") (pinfunction "1_M2") (pintype "bidirectional"))
    )
    (net (code "71") (name "Net-(P5D-S)") (class "Default")
      (node (ref "P5") (pin "12") (pinfunction "S_12") (pintype "passive"))
      (node (ref "U$1") (pin "N2") (pinfunction "1_N2") (pintype "bidirectional"))
    )
    (net (code "72") (name "Net-(P5E-S)") (class "Default")
      (node (ref "P5") (pin "13") (pinfunction "S_13") (pintype "passive"))
      (node (ref "U$1") (pin "P2") (pinfunction "1_P2") (pintype "bidirectional"))
    )
    (net (code "73") (name "Net-(P5F-S)") (class "Default")
      (node (ref "P5") (pin "14") (pinfunction "S_14") (pintype "passive"))
      (node (ref "U$1") (pin "R2") (pinfunction "1_R2") (pintype "bidirectional"))
    )
    (net (code "74") (name "Net-(P5G-S)") (class "Default")
      (node (ref "P5") (pin "15") (pinfunction "S_15") (pintype "passive"))
      (node (ref "U$1") (pin "S2") (pinfunction "1_S2") (pintype "bidirectional"))
    )
    (net (code "75") (name "Net-(P5H-S)") (class "Default")
      (node (ref "P5") (pin "16") (pinfunction "S_16") (pintype "passive"))
      (node (ref "U$1") (pin "T2") (pinfunction "1_T2") (pintype "bidirectional"))
    )
    (net (code "76") (name "Net-(P5I-S)") (class "Default")
      (node (ref "P5") (pin "17") (pinfunction "S_17") (pintype "passive"))
      (node (ref "U$1") (pin "U2") (pinfunction "1_U2") (pintype "bidirectional"))
    )
    (net (code "77") (name "Net-(P5K-S)") (class "Default")
      (node (ref "P5") (pin "19") (pinfunction "S_19") (pintype "passive"))
      (node (ref "U$1") (pin "V2") (pinfunction "1_V2") (pintype "bidirectional"))
    )
    (net (code "78") (name "Net-(P5N-S)") (class "Default")
      (node (ref "P5") (pin "3") (pinfunction "S_3") (pintype "passive"))
      (node (ref "U$1") (pin "C2") (pinfunction "1_C2") (pintype "bidirectional"))
    )
    (net (code "79") (name "Net-(P5O-S)") (class "Default")
      (node (ref "P5") (pin "4") (pinfunction "S_4") (pintype "passive"))
      (node (ref "U$1") (pin "D2") (pinfunction "1_D2") (pintype "bidirectional"))
    )
    (net (code "80") (name "Net-(P5P-S)") (class "Default")
      (node (ref "P5") (pin "5") (pinfunction "S_5") (pintype "passive"))
      (node (ref "U$1") (pin "E2") (pinfunction "1_E2") (pintype "bidirectional"))
    )
    (net (code "81") (name "Net-(P5Q-S)") (class "Default")
      (node (ref "P5") (pin "6") (pinfunction "S_6") (pintype "passive"))
      (node (ref "U$1") (pin "F2") (pinfunction "1_F2") (pintype "bidirectional"))
    )
    (net (code "82") (name "Net-(P5R-S)") (class "Default")
      (node (ref "P5") (pin "7") (pinfunction "S_7") (pintype "passive"))
      (node (ref "U$1") (pin "H2") (pinfunction "1_H2") (pintype "bidirectional"))
    )
    (net (code "83") (name "Net-(P5S-S)") (class "Default")
      (node (ref "P5") (pin "8") (pinfunction "S_8") (pintype "passive"))
      (node (ref "U$1") (pin "J2") (pinfunction "1_J2") (pintype "bidirectional"))
    )
    (net (code "84") (name "Net-(P5T-S)") (class "Default")
      (node (ref "P5") (pin "9") (pinfunction "S_9") (pintype "passive"))
      (node (ref "U$1") (pin "K2") (pinfunction "1_K2") (pintype "bidirectional"))
    )
    (net (code "85") (name "Net-(P6B-S)") (class "Default")
      (node (ref "P6") (pin "10") (pinfunction "S_10") (pintype "passive"))
      (node (ref "U$2") (pin "L2") (pinfunction "1_L2") (pintype "bidirectional"))
    )
    (net (code "86") (name "Net-(P6C-S)") (class "Default")
      (node (ref "P6") (pin "11") (pinfunction "S_11") (pintype "passive"))
      (node (ref "R35") (pin "2") (pinfunction "2_2") (pintype "passive"))
    )
    (net (code "87") (name "Net-(P6D-S)") (class "Default")
      (node (ref "P6") (pin "12") (pinfunction "S_12") (pintype "passive"))
      (node (ref "U$2") (pin "N2") (pinfunction "1_N2") (pintype "bidirectional"))
    )
    (net (code "88") (name "Net-(P6E-S)") (class "Default")
      (node (ref "P6") (pin "13") (pinfunction "S_13") (pintype "passive"))
      (node (ref "U$2") (pin "P2") (pinfunction "1_P2") (pintype "bidirectional"))
    )
    (net (code "89") (name "Net-(P6F-S)") (class "Default")
      (node (ref "P6") (pin "14") (pinfunction "S_14") (pintype "passive"))
      (node (ref "U$2") (pin "R2") (pinfunction "1_R2") (pintype "bidirectional"))
    )
    (net (code "90") (name "Net-(P6G-S)") (class "Default")
      (node (ref "P6") (pin "15") (pinfunction "S_15") (pintype "passive"))
      (node (ref "R34") (pin "2") (pinfunction "2_2") (pintype "passive"))
    )
    (net (code "91") (name "Net-(P6H-S)") (class "Default")
      (node (ref "P6") (pin "16") (pinfunction "S_16") (pintype "passive"))
      (node (ref "U$2") (pin "T2") (pinfunction "1_T2") (pintype "bidirectional"))
    )
    (net (code "92") (name "Net-(P6I-S)") (class "Default")
      (node (ref "P6") (pin "17") (pinfunction "S_17") (pintype "passive"))
      (node (ref "U$2") (pin "U2") (pinfunction "1_U2") (pintype "bidirectional"))
    )
    (net (code "93") (name "Net-(P6K-S)") (class "Default")
      (node (ref "P6") (pin "19") (pinfunction "S_19") (pintype "passive"))
      (node (ref "U$2") (pin "V2") (pinfunction "1_V2") (pintype "bidirectional"))
    )
    (net (code "94") (name "Net-(P6N-S)") (class "Default")
      (node (ref "P6") (pin "3") (pinfunction "S_3") (pintype "passive"))
      (node (ref "U$2") (pin "C2") (pinfunction "1_C2") (pintype "bidirectional"))
    )
    (net (code "95") (name "Net-(P6O-S)") (class "Default")
      (node (ref "P6") (pin "4") (pinfunction "S_4") (pintype "passive"))
      (node (ref "R39") (pin "2") (pinfunction "2_2") (pintype "passive"))
    )
    (net (code "96") (name "Net-(P6P-S)") (class "Default")
      (node (ref "P6") (pin "5") (pinfunction "S_5") (pintype "passive"))
      (node (ref "R38") (pin "2") (pinfunction "2_2") (pintype "passive"))
    )
    (net (code "97") (name "Net-(P6Q-S)") (class "Default")
      (node (ref "P6") (pin "6") (pinfunction "S_6") (pintype "passive"))
      (node (ref "U$2") (pin "F2") (pinfunction "1_F2") (pintype "bidirectional"))
    )
    (net (code "98") (name "Net-(P6R-S)") (class "Default")
      (node (ref "P6") (pin "7") (pinfunction "S_7") (pintype "passive"))
      (node (ref "R37") (pin "2") (pinfunction "2_2") (pintype "passive"))
    )
    (net (code "99") (name "Net-(P6S-S)") (class "Default")
      (node (ref "P6") (pin "8") (pinfunction "S_8") (pintype "passive"))
      (node (ref "U$2") (pin "J2") (pinfunction "1_J2") (pintype "bidirectional"))
    )
    (net (code "100") (name "Net-(P6T-S)") (class "Default")
      (node (ref "P6") (pin "9") (pinfunction "S_9") (pintype "passive"))
      (node (ref "R36") (pin "2") (pinfunction "2_2") (pintype "passive"))
    )
    (net (code "101") (name "Net-(Q1-B)") (class "Default")
      (node (ref "D2") (pin "C") (pinfunction "C_C") (pintype "passive"))
      (node (ref "D3") (pin "C") (pinfunction "C_C") (pintype "passive"))
      (node (ref "Q1") (pin "2") (pinfunction "B_2") (pintype "passive"))
      (node (ref "R9") (pin "2") (pinfunction "2_2") (pintype "passive"))
    )
    (net (code "102") (name "Net-(Q2-B)") (class "Default")
      (node (ref "D4") (pin "C") (pinfunction "C_C") (pintype "passive"))
      (node (ref "D6") (pin "C") (pinfunction "C_C") (pintype "passive"))
      (node (ref "Q2") (pin "2") (pinfunction "B_2") (pintype "passive"))
      (node (ref "R11") (pin "2") (pinfunction "2_2") (pintype "passive"))
    )
    (net (code "103") (name "Net-(Q3-B)") (class "Default")
      (node (ref "D7") (pin "C") (pinfunction "C_C") (pintype "passive"))
      (node (ref "D9") (pin "C") (pinfunction "C_C") (pintype "passive"))
      (node (ref "Q3") (pin "2") (pinfunction "B_2") (pintype "passive"))
      (node (ref "R13") (pin "2") (pinfunction "2_2") (pintype "passive"))
    )
    (net (code "104") (name "Net-(Q4-B)") (class "Default")
      (node (ref "D10") (pin "C") (pinfunction "C_C") (pintype "passive"))
      (node (ref "D12") (pin "C") (pinfunction "C_C") (pintype "passive"))
      (node (ref "Q4") (pin "2") (pinfunction "B_2") (pintype "passive"))
      (node (ref "R15") (pin "2") (pinfunction "2_2") (pintype "passive"))
    )
    (net (code "105") (name "Net-(Q5-B)") (class "Default")
      (node (ref "D13") (pin "C") (pinfunction "C_C") (pintype "passive"))
      (node (ref "D15") (pin "C") (pinfunction "C_C") (pintype "passive"))
      (node (ref "Q5") (pin "2") (pinfunction "B_2") (pintype "passive"))
      (node (ref "R17") (pin "2") (pinfunction "2_2") (pintype "passive"))
    )
    (net (code "106") (name "Net-(Q6-B)") (class "Default")
      (node (ref "D16") (pin "C") (pinfunction "C_C") (pintype "passive"))
      (node (ref "D18") (pin "C") (pinfunction "C_C") (pintype "passive"))
      (node (ref "Q6") (pin "2") (pinfunction "B_2") (pintype "passive"))
      (node (ref "R21") (pin "2") (pinfunction "2_2") (pintype "passive"))
    )
    (net (code "107") (name "Net-(Q7-B)") (class "Default")
      (node (ref "D19") (pin "C") (pinfunction "C_C") (pintype "passive"))
      (node (ref "D21") (pin "C") (pinfunction "C_C") (pintype "passive"))
      (node (ref "Q7") (pin "2") (pinfunction "B_2") (pintype "passive"))
      (node (ref "R23") (pin "2") (pinfunction "2_2") (pintype "passive"))
    )
    (net (code "108") (name "Net-(Q8-B)") (class "Default")
      (node (ref "D22") (pin "C") (pinfunction "C_C") (pintype "passive"))
      (node (ref "D24") (pin "C") (pinfunction "C_C") (pintype "passive"))
      (node (ref "Q8") (pin "2") (pinfunction "B_2") (pintype "passive"))
      (node (ref "R25") (pin "2") (pinfunction "2_2") (pintype "passive"))
    )
    (net (code "109") (name "Net-(Q9-B)") (class "Default")
      (node (ref "D25") (pin "C") (pinfunction "C_C") (pintype "passive"))
      (node (ref "D27") (pin "C") (pinfunction "C_C") (pintype "passive"))
      (node (ref "Q9") (pin "2") (pinfunction "B_2") (pintype "passive"))
      (node (ref "R29") (pin "2") (pinfunction "2_2") (pintype "passive"))
    )
    (net (code "110") (name "Net-(U$2D-1)") (class "Default")
      (node (ref "R39") (pin "1") (pinfunction "1_1") (pintype "passive"))
      (node (ref "R40") (pin "1") (pinfunction "1_1") (pintype "passive"))
      (node (ref "U$2") (pin "D2") (pinfunction "1_D2") (pintype "bidirectional"))
    )
    (net (code "111") (name "Net-(U$2E-1)") (class "Default")
      (node (ref "R38") (pin "1") (pinfunction "1_1") (pintype "passive"))
      (node (ref "R41") (pin "1") (pinfunction "1_1") (pintype "passive"))
      (node (ref "U$2") (pin "E2") (pinfunction "1_E2") (pintype "bidirectional"))
    )
    (net (code "112") (name "Net-(U$2G-1)") (class "Default")
      (node (ref "R37") (pin "1") (pinfunction "1_1") (pintype "passive"))
      (node (ref "R42") (pin "1") (pinfunction "1_1") (pintype "passive"))
      (node (ref "U$2") (pin "H2") (pinfunction "1_H2") (pintype "bidirectional"))
    )
    (net (code "113") (name "Net-(U$2I-1)") (class "Default")
      (node (ref "R36") (pin "1") (pinfunction "1_1") (pintype "passive"))
      (node (ref "R43") (pin "1") (pinfunction "1_1") (pintype "passive"))
      (node (ref "U$2") (pin "K2") (pinfunction "1_K2") (pintype "bidirectional"))
    )
    (net (code "114") (name "Net-(U$2K-1)") (class "Default")
      (node (ref "R35") (pin "1") (pinfunction "1_1") (pintype "passive"))
      (node (ref "R44") (pin "1") (pinfunction "1_1") (pintype "passive"))
      (node (ref "U$2") (pin "M2") (pinfunction "1_M2") (pintype "bidirectional"))
    )
    (net (code "115") (name "Net-(U$2O-1)") (class "Default")
      (node (ref "R34") (pin "1") (pinfunction "1_1") (pintype "passive"))
      (node (ref "R45") (pin "1") (pinfunction "1_1") (pintype "passive"))
      (node (ref "U$2") (pin "S2") (pinfunction "1_S2") (pintype "bidirectional"))
    )
    (net (code "116") (name "Net-(U2A-FB1MC18)") (class "Default")
      (node (ref "R31") (pin "1") (pinfunction "1_1") (pintype "passive"))
      (node (ref "SW1") (pin "1") (pinfunction "1_1") (pintype "passive"))
      (node (ref "U2") (pin "24") (pinfunction "FB1MC18_24") (pintype "bidirectional"))
    )
    (net (code "117") (name "Net-(U2A-FB3MC1)") (class "Default")
      (node (ref "R32") (pin "1") (pinfunction "1_1") (pintype "passive"))
      (node (ref "SW1") (pin "2") (pinfunction "2_2") (pintype "passive"))
      (node (ref "U2") (pin "25") (pinfunction "FB3MC1_25") (pintype "bidirectional"))
    )
    (net (code "118") (name "Net-(U2A-FB3MC9)") (class "Default")
      (node (ref "R33") (pin "1") (pinfunction "1_1") (pintype "passive"))
      (node (ref "SW1") (pin "4") (pinfunction "4_4") (pintype "passive"))
      (node (ref "U2") (pin "26") (pinfunction "FB3MC9_26") (pintype "bidirectional"))
    )
    (net (code "119") (name "Net-(U2B-TCK)") (class "Default")
      (node (ref "P4") (pin "4") (pinfunction "4_4") (pintype "passive"))
      (node (ref "U2") (pin "30") (pinfunction "TCK_30") (pintype "input"))
    )
    (net (code "120") (name "Net-(U2B-TDI)") (class "Default")
      (node (ref "P4") (pin "2") (pinfunction "2_2") (pintype "passive"))
      (node (ref "U2") (pin "28") (pinfunction "TDI_28") (pintype "input"))
    )
    (net (code "121") (name "Net-(U2B-TDO)") (class "Default")
      (node (ref "P4") (pin "3") (pinfunction "3_3") (pintype "passive"))
      (node (ref "U2") (pin "59") (pinfunction "TDO_59") (pintype "output"))
    )
    (net (code "122") (name "Net-(U2B-TMS)") (class "Default")
      (node (ref "P4") (pin "1") (pinfunction "1_1") (pintype "passive"))
      (node (ref "U2") (pin "29") (pinfunction "TMS_29") (pintype "input"))
    )
    (net (code "123") (name "Net-(X1-OUT)") (class "Default")
      (node (ref "U2") (pin "9") (pinfunction "GCK_9") (pintype "input"))
      (node (ref "X1") (pin "8") (pinfunction "OUT_8") (pintype "output"))
    )
    (net (code "124") (name "PSM") (class "Default")
      (node (ref "D16") (pin "A") (pinfunction "A_A") (pintype "passive"))
      (node (ref "P1") (pin "T2") (pinfunction "1_T2") (pintype "bidirectional"))
      (node (ref "Q6") (pin "3") (pinfunction "C_3") (pintype "passive"))
      (node (ref "R22") (pin "2") (pinfunction "2_2") (pintype "passive"))
    )
    (net (code "125") (name "T1D") (class "Default")
      (node (ref "D19") (pin "A") (pinfunction "A_A") (pintype "passive"))
      (node (ref "P1") (pin "V2") (pinfunction "1_V2") (pintype "bidirectional"))
      (node (ref "Q7") (pin "3") (pinfunction "C_3") (pintype "passive"))
      (node (ref "R24") (pin "2") (pinfunction "2_2") (pintype "passive"))
    )
    (net (code "126") (name "TBD") (class "Default")
      (node (ref "D7") (pin "A") (pinfunction "A_A") (pintype "passive"))
      (node (ref "P1") (pin "H2") (pinfunction "1_H2") (pintype "bidirectional"))
      (node (ref "Q3") (pin "3") (pinfunction "C_3") (pintype "passive"))
      (node (ref "R14") (pin "2") (pinfunction "2_2") (pintype "passive"))
    )
    (net (code "127") (name "TTA") (class "Default")
      (node (ref "D3") (pin "A") (pinfunction "A_A") (pintype "passive"))
      (node (ref "P1") (pin "D2") (pinfunction "1_D2") (pintype "bidirectional"))
      (node (ref "Q1") (pin "3") (pinfunction "C_3") (pintype "passive"))
      (node (ref "R10") (pin "2") (pinfunction "2_2") (pintype "passive"))
    )
    (net (code "128") (name "TTB") (class "Default")
      (node (ref "D4") (pin "A") (pinfunction "A_A") (pintype "passive"))
      (node (ref "P1") (pin "E2") (pinfunction "1_E2") (pintype "bidirectional"))
      (node (ref "Q2") (pin "3") (pinfunction "C_3") (pintype "passive"))
      (node (ref "R12") (pin "2") (pinfunction "2_2") (pintype "passive"))
    )
    (net (code "129") (name "VCC") (class "Default")
      (node (ref "C1") (pin "1") (pinfunction "1_1") (pintype "passive"))
      (node (ref "C2") (pin "1") (pinfunction "1_1") (pintype "passive"))
      (node (ref "C3") (pin "1") (pinfunction "1_1") (pintype "passive"))
      (node (ref "C4") (pin "1") (pinfunction "1_1") (pintype "passive"))
      (node (ref "C5") (pin "+") (pinfunction "+_+") (pintype "passive"))
      (node (ref "P4") (pin "6") (pinfunction "6_6") (pintype "passive"))
      (node (ref "R31") (pin "2") (pinfunction "2_2") (pintype "passive"))
      (node (ref "R32") (pin "2") (pinfunction "2_2") (pintype "passive"))
      (node (ref "R33") (pin "2") (pinfunction "2_2") (pintype "passive"))
      (node (ref "U1") (pin "3") (pinfunction "VO_3") (pintype "passive"))
      (node (ref "X1") (pin "14") (pinfunction "VCC_14") (pintype "power_in"))
    )
    (net (code "130") (name "VDD") (class "Default")
      (node (ref "R40") (pin "2") (pinfunction "2_2") (pintype "passive"))
      (node (ref "R41") (pin "2") (pinfunction "2_2") (pintype "passive"))
      (node (ref "R42") (pin "2") (pinfunction "2_2") (pintype "passive"))
      (node (ref "R43") (pin "2") (pinfunction "2_2") (pintype "passive"))
      (node (ref "R44") (pin "2") (pinfunction "2_2") (pintype "passive"))
      (node (ref "R45") (pin "2") (pinfunction "2_2") (pintype "passive"))
      (node (ref "U$2") (pin "A2") (pinfunction "1_A2") (pintype "bidirectional"))
    )
    (net (code "131") (name "WFF") (class "Default")
      (node (ref "P1") (pin "P2") (pinfunction "1_P2") (pintype "bidirectional"))
      (node (ref "R18") (pin "1") (pinfunction "1_1") (pintype "passive"))
    )
    (net (code "132") (name "WLO") (class "Default")
      (node (ref "P3") (pin "15") (pinfunction "S_15") (pintype "passive"))
      (node (ref "U2") (pin "21") (pinfunction "FB3MC8_21") (pintype "bidirectional"))
    )
    (net (code "133") (name "WTE") (class "Default")
      (node (ref "P1") (pin "M2") (pinfunction "1_M2") (pintype "bidirectional"))
      (node (ref "R19") (pin "1") (pinfunction "1_1") (pintype "passive"))
    )
    (net (code "134") (name "X0") (class "Default")
      (node (ref "P2") (pin "4") (pinfunction "S_4") (pintype "passive"))
      (node (ref "R1") (pin "1") (pinfunction "1_1") (pintype "passive"))
    )
    (net (code "135") (name "X1") (class "Default")
      (node (ref "P2") (pin "5") (pinfunction "S_5") (pintype "passive"))
      (node (ref "R2") (pin "1") (pinfunction "1_1") (pintype "passive"))
    )
    (net (code "136") (name "X2") (class "Default")
      (node (ref "P2") (pin "7") (pinfunction "S_7") (pintype "passive"))
      (node (ref "R3") (pin "1") (pinfunction "1_1") (pintype "passive"))
    )
    (net (code "137") (name "X3") (class "Default")
      (node (ref "P2") (pin "9") (pinfunction "S_9") (pintype "passive"))
      (node (ref "R4") (pin "1") (pinfunction "1_1") (pintype "passive"))
    )
    (net (code "138") (name "X4") (class "Default")
      (node (ref "P2") (pin "11") (pinfunction "S_11") (pintype "passive"))
      (node (ref "R5") (pin "1") (pinfunction "1_1") (pintype "passive"))
    )
    (net (code "139") (name "X5") (class "Default")
      (node (ref "P2") (pin "13") (pinfunction "S_13") (pintype "passive"))
      (node (ref "R6") (pin "1") (pinfunction "1_1") (pintype "passive"))
    )
    (net (code "140") (name "X6") (class "Default")
      (node (ref "P2") (pin "15") (pinfunction "S_15") (pintype "passive"))
      (node (ref "R7") (pin "1") (pinfunction "1_1") (pintype "passive"))
    )
    (net (code "141") (name "X7") (class "Default")
      (node (ref "P2") (pin "16") (pinfunction "S_16") (pintype "passive"))
      (node (ref "R8") (pin "1") (pinfunction "1_1") (pintype "passive"))
    )
    (net (code "142") (name "unconnected-(SW1-Pad8)") (class "Default")
      (node (ref "SW1") (pin "8") (pinfunction "8_8") (pintype "passive"))
    )
    (net (code "143") (name "unconnected-(U2A-FB1MC3-Pad6)") (class "Default")
      (node (ref "U2") (pin "6") (pinfunction "FB1MC3_6") (pintype "bidirectional"))
    )
    (net (code "144") (name "unconnected-(U2A-FB1MC10-Pad13)") (class "Default")
      (node (ref "U2") (pin "13") (pinfunction "FB1MC10_13") (pintype "bidirectional"))
    )
    (net (code "145") (name "unconnected-(U2A-FB1MC15-Pad14)") (class "Default")
      (node (ref "U2") (pin "14") (pinfunction "FB1MC15_14") (pintype "bidirectional"))
    )
    (net (code "146") (name "unconnected-(U2A-FB1MC16-Pad23)") (class "Default")
      (node (ref "U2") (pin "23") (pinfunction "FB1MC16_23") (pintype "bidirectional"))
    )
    (net (code "147") (name "unconnected-(U2A-FB2MC17-Pad84)") (class "Default")
      (node (ref "U2") (pin "84") (pinfunction "FB2MC17_84") (pintype "bidirectional"))
    )
    (net (code "148") (name "unconnected-(U2A-FB3MC14-Pad36)") (class "Default")
      (node (ref "U2") (pin "36") (pinfunction "FB3MC14_36") (pintype "bidirectional"))
    )
    (net (code "149") (name "unconnected-(U2A-FB3MC15-Pad37)") (class "Default")
      (node (ref "U2") (pin "37") (pinfunction "FB3MC15_37") (pintype "bidirectional"))
    )
    (net (code "150") (name "unconnected-(U2A-FB4MC2-Pad44)") (class "Default")
      (node (ref "U2") (pin "44") (pinfunction "FB4MC2_44") (pintype "bidirectional"))
    )
    (net (code "151") (name "~{CE}") (class "Default")
      (node (ref "U2") (pin "58") (pinfunction "FB4MC12_58") (pintype "bidirectional"))
      (node (ref "U3") (pin "24") (pinfunction "CE_24") (pintype "input"))
    )
    (net (code "152") (name "~{OE}") (class "Default")
      (node (ref "U2") (pin "66") (pinfunction "FB4MC17_66") (pintype "bidirectional"))
      (node (ref "U3") (pin "26") (pinfunction "OE_26") (pintype "input"))
    )
    (net (code "153") (name "~{WE}") (class "Default")
      (node (ref "U2") (pin "75") (pinfunction "FB2MC10_75") (pintype "bidirectional"))
      (node (ref "U3") (pin "31") (pinfunction "WE_31") (pintype "input"))
    )
  )
)
